# 13_Temp.net
KiCad netlist of a schematic drawn in Altium Designer
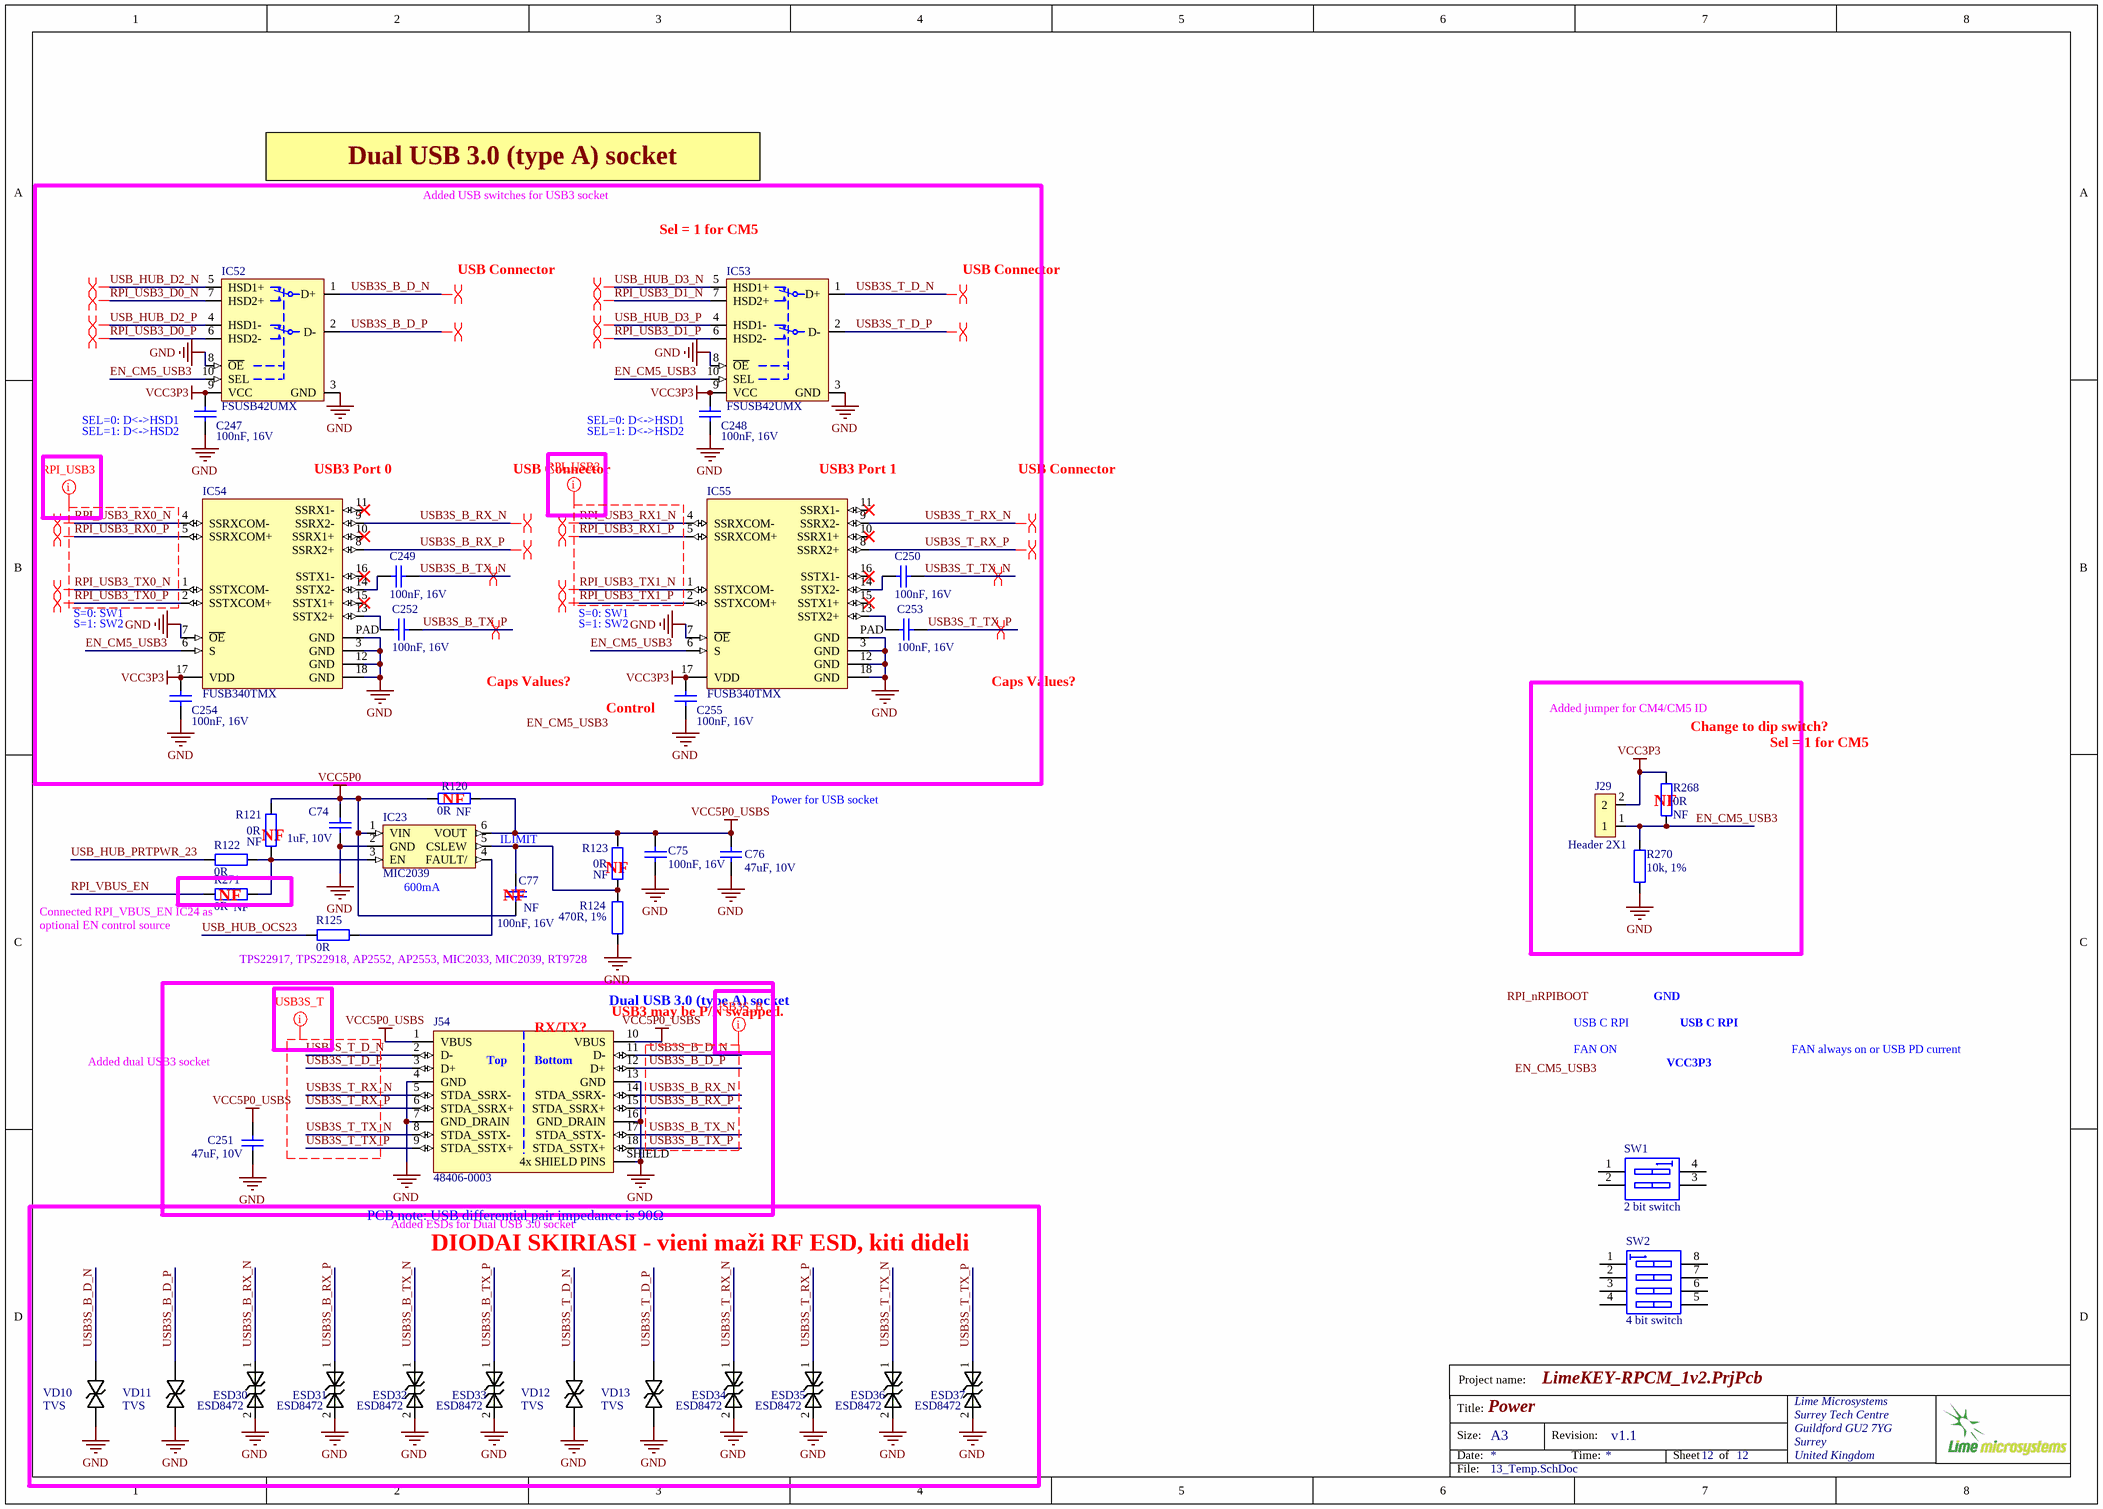
[diagram p0: 13_Temp.SchDoc]

(export (version "E")
  (design (tool "Eeschema 10.0.6"))
  (components
    (comp (ref "C74")
      (value "1uF, 10V")
      (footprint "CAP0402")
      (fields (field (name "MANUFACTURER") "Yageo"))
      (libsource (lib "") (part "Cap_0402_1"))
    )
    (comp (ref "C75")
      (value "100nF, 16V")
      (footprint "CAP0402")
      (fields
        (field (name "MANUFACTURER") "Murata Electronics")
        (field (name "TOLERANCE") "10 %")
        (field (name "MANUFACTURER PART NUMBER") "GRM155R71C104KA88D")
      )
      (libsource (lib "") (part "Cap_0402_1"))
    )
    (comp (ref "C76")
      (value "47uF, 10V")
      (footprint "CAP1206")
      (fields (field (name "TOLERANCE") "±20%") (field (name "MANUFACTURER") "TDK Corporation"))
      (libsource (lib "LimeFPGAboard_schLib") (part "Cap_1206"))
    )
    (comp (ref "C77")
      (value "100nF, 16V")
      (footprint "CAP0402")
      (fields
        (field (name "ASSEMBLY INFO") "NF")
        (field (name "MANUFACTURER") "Murata Electronics")
        (field (name "TOLERANCE") "10 %")
        (field (name "MANUFACTURER PART NUMBER") "GRM155R71C104KA88D")
      )
      (libsource (lib "") (part "Cap_0402_1"))
    )
    (comp (ref "C247")
      (value "100nF, 16V")
      (footprint "CAP0402")
      (fields
        (field (name "MANUFACTURER") "Murata Electronics")
        (field (name "TOLERANCE") "10 %")
        (field (name "MANUFACTURER PART NUMBER") "GRM155R71C104KA88D")
      )
      (libsource (lib "LimeMicroAltiumLib_schLib") (part "Cap_0402"))
    )
    (comp (ref "C248")
      (value "100nF, 16V")
      (footprint "CAP0402")
      (fields
        (field (name "MANUFACTURER") "Murata Electronics")
        (field (name "TOLERANCE") "10 %")
        (field (name "MANUFACTURER PART NUMBER") "GRM155R71C104KA88D")
      )
      (libsource (lib "LimeMicroAltiumLib_schLib") (part "Cap_0402"))
    )
    (comp (ref "C249")
      (value "100nF, 16V")
      (footprint "CAP0402")
      (fields
        (field (name "MANUFACTURER") "Murata Electronics")
        (field (name "TOLERANCE") "10 %")
        (field (name "MANUFACTURER PART NUMBER") "GRM155R71C104KA88D")
      )
      (libsource (lib "LimeMicroAltiumLib_schLib") (part "Cap_0402"))
    )
    (comp (ref "C250")
      (value "100nF, 16V")
      (footprint "CAP0402")
      (fields
        (field (name "MANUFACTURER") "Murata Electronics")
        (field (name "TOLERANCE") "10 %")
        (field (name "MANUFACTURER PART NUMBER") "GRM155R71C104KA88D")
      )
      (libsource (lib "LimeMicroAltiumLib_schLib") (part "Cap_0402"))
    )
    (comp (ref "C251")
      (value "47uF, 10V")
      (footprint "CAP1206")
      (fields (field (name "TOLERANCE") "±20%") (field (name "MANUFACTURER") "TDK Corporation"))
      (libsource (lib "LimeFPGAboard_schLib") (part "Cap_1206"))
    )
    (comp (ref "C252")
      (value "100nF, 16V")
      (footprint "CAP0402")
      (fields
        (field (name "MANUFACTURER") "Murata Electronics")
        (field (name "TOLERANCE") "10 %")
        (field (name "MANUFACTURER PART NUMBER") "GRM155R71C104KA88D")
      )
      (libsource (lib "LimeMicroAltiumLib_schLib") (part "Cap_0402"))
    )
    (comp (ref "C253")
      (value "100nF, 16V")
      (footprint "CAP0402")
      (fields
        (field (name "MANUFACTURER") "Murata Electronics")
        (field (name "TOLERANCE") "10 %")
        (field (name "MANUFACTURER PART NUMBER") "GRM155R71C104KA88D")
      )
      (libsource (lib "LimeMicroAltiumLib_schLib") (part "Cap_0402"))
    )
    (comp (ref "C254")
      (value "100nF, 16V")
      (footprint "CAP0402")
      (fields
        (field (name "MANUFACTURER") "Murata Electronics")
        (field (name "TOLERANCE") "10 %")
        (field (name "MANUFACTURER PART NUMBER") "GRM155R71C104KA88D")
      )
      (libsource (lib "LimeMicroAltiumLib_schLib") (part "Cap_0402"))
    )
    (comp (ref "C255")
      (value "100nF, 16V")
      (footprint "CAP0402")
      (fields
        (field (name "MANUFACTURER") "Murata Electronics")
        (field (name "TOLERANCE") "10 %")
        (field (name "MANUFACTURER PART NUMBER") "GRM155R71C104KA88D")
      )
      (libsource (lib "LimeMicroAltiumLib_schLib") (part "Cap_0402"))
    )
    (comp (ref "ESD30")
      (value "ESD8472")
      (footprint "ESD8472_X3DFN2")
      (fields (field (name "MANUFACTURER") "ON Semiconductor"))
      (libsource (lib "LimeMicroAltiumLib_schLib") (part "ESD8472"))
    )
    (comp (ref "ESD31")
      (value "ESD8472")
      (footprint "ESD8472_X3DFN2")
      (fields (field (name "MANUFACTURER") "ON Semiconductor"))
      (libsource (lib "LimeMicroAltiumLib_schLib") (part "ESD8472"))
    )
    (comp (ref "ESD32")
      (value "ESD8472")
      (footprint "ESD8472_X3DFN2")
      (fields (field (name "MANUFACTURER") "ON Semiconductor"))
      (libsource (lib "LimeMicroAltiumLib_schLib") (part "ESD8472"))
    )
    (comp (ref "ESD33")
      (value "ESD8472")
      (footprint "ESD8472_X3DFN2")
      (fields (field (name "MANUFACTURER") "ON Semiconductor"))
      (libsource (lib "LimeMicroAltiumLib_schLib") (part "ESD8472"))
    )
    (comp (ref "ESD34")
      (value "ESD8472")
      (footprint "ESD8472_X3DFN2")
      (fields (field (name "MANUFACTURER") "ON Semiconductor"))
      (libsource (lib "LimeMicroAltiumLib_schLib") (part "ESD8472"))
    )
    (comp (ref "ESD35")
      (value "ESD8472")
      (footprint "ESD8472_X3DFN2")
      (fields (field (name "MANUFACTURER") "ON Semiconductor"))
      (libsource (lib "LimeMicroAltiumLib_schLib") (part "ESD8472"))
    )
    (comp (ref "ESD36")
      (value "ESD8472")
      (footprint "ESD8472_X3DFN2")
      (fields (field (name "MANUFACTURER") "ON Semiconductor"))
      (libsource (lib "LimeMicroAltiumLib_schLib") (part "ESD8472"))
    )
    (comp (ref "ESD37")
      (value "ESD8472")
      (footprint "ESD8472_X3DFN2")
      (fields (field (name "MANUFACTURER") "ON Semiconductor"))
      (libsource (lib "LimeMicroAltiumLib_schLib") (part "ESD8472"))
    )
    (comp (ref "IC23")
      (value "MIC2039")
      (footprint "SOT23-6")
      (fields (field (name "MANUFACTURER") "Microchip"))
      (libsource (lib "LimeMicroAltiumLib_schLib_r04") (part "MIC2033_power_switch"))
    )
    (comp (ref "IC52")
      (value "FSUSB42UMX")
      (footprint "FSUSB42UMX")
      (fields (field (name "MANUFACTURER") "ON Semiconductor") (field (name "BASE PART NUMBER") "FSUSB42"))
      (libsource (lib "LimeMicroAltiumLib_schLib_r01") (part "FSUSB42UMX"))
    )
    (comp (ref "IC53")
      (value "FSUSB42UMX")
      (footprint "FSUSB42UMX")
      (fields (field (name "MANUFACTURER") "ON Semiconductor") (field (name "BASE PART NUMBER") "FSUSB42"))
      (libsource (lib "LimeMicroAltiumLib_schLib_r01") (part "FSUSB42UMX"))
    )
    (comp (ref "IC54")
      (value "FUSB340TMX")
      (footprint "FUSB340TMX_USB_switch_18-XFQFN")
      (fields (field (name "MANUFACTURER") "ON Semiconductor / Fairchild"))
      (libsource (lib "LimeMicroAltiumLib") (part "FUSB340TMX_USB_switch"))
    )
    (comp (ref "IC55")
      (value "FUSB340TMX")
      (footprint "FUSB340TMX_USB_switch_18-XFQFN")
      (fields (field (name "MANUFACTURER") "ON Semiconductor / Fairchild"))
      (libsource (lib "LimeMicroAltiumLib") (part "FUSB340TMX_USB_switch"))
    )
    (comp (ref "J29")
      (value "Header 2X1")
      (footprint "HDR_1x2")
      (fields (field (name "MANUFACTURER") "3M"))
      (libsource (lib "LimeFPGAboard_schLib") (part "Jumper"))
    )
    (comp (ref "J54")
      (value "48406-0003")
      (footprint "Dual_USB_48406-0003_Molex")
      (fields (field (name "MANUFACTURER") "Molex"))
      (libsource (lib "LimeMicroAltiumLib") (part "Dual_USB_48406-0003_Molex"))
    )
    (comp (ref "R120")
      (value "0R")
      (footprint "RES0402")
      (fields
        (field (name "ASSEMBLY INFO") "NF")
        (field (name "MANUFACTURER") "Yageo")
        (field (name "TOLERANCE") "Jumper")
      )
      (libsource (lib "LimeMicroAltiumLib_schLib") (part "Res_0402"))
    )
    (comp (ref "R121")
      (value "0R")
      (footprint "RES0402")
      (fields
        (field (name "ASSEMBLY INFO") "NF")
        (field (name "MANUFACTURER") "Yageo")
        (field (name "TOLERANCE") "Jumper")
      )
      (libsource (lib "LimeMicroAltiumLib_schLib") (part "Res_0402"))
    )
    (comp (ref "R122")
      (value "0R")
      (footprint "RES0402")
      (fields (field (name "MANUFACTURER") "Yageo") (field (name "TOLERANCE") "Jumper"))
      (libsource (lib "LimeMicroAltiumLib_schLib") (part "Res_0402"))
    )
    (comp (ref "R123")
      (value "0R")
      (footprint "RES0402")
      (fields
        (field (name "ASSEMBLY INFO") "NF")
        (field (name "MANUFACTURER") "Yageo")
        (field (name "TOLERANCE") "Jumper")
      )
      (libsource (lib "LimeMicroAltiumLib_schLib") (part "Res_0402"))
    )
    (comp (ref "R124")
      (value "470R, 1%")
      (footprint "RES0402")
      (fields (field (name "TOLERANCE") "1%") (field (name "MANUFACTURER") "Yageo"))
      (libsource (lib "LimeMicroAltiumLib_schLib") (part "Res_0402"))
    )
    (comp (ref "R125")
      (value "0R")
      (footprint "RES0402")
      (fields (field (name "MANUFACTURER") "Yageo") (field (name "TOLERANCE") "Jumper"))
      (libsource (lib "LimeMicroAltiumLib_schLib") (part "Res_0402"))
    )
    (comp (ref "R268")
      (value "0R")
      (footprint "RES0402")
      (fields
        (field (name "ASSEMBLY INFO") "NF")
        (field (name "MANUFACTURER") "Yageo")
        (field (name "TOLERANCE") "Jumper")
      )
      (libsource (lib "") (part "Res_0402_1"))
    )
    (comp (ref "R270")
      (value "10k, 1%")
      (footprint "RES0402")
      (fields (field (name "MANUFACTURER") "Yageo") (field (name "TOLERANCE") "±1%"))
      (libsource (lib "") (part "Res_0402_1"))
    )
    (comp (ref "R271")
      (value "0R")
      (footprint "RES0402")
      (fields
        (field (name "ASSEMBLY INFO") "NF")
        (field (name "MANUFACTURER") "Yageo")
        (field (name "TOLERANCE") "Jumper")
      )
      (libsource (lib "LimeMicroAltiumLib_schLib") (part "Res_0402"))
    )
    (comp (ref "SW1")
      (value "2 bit switch")
      (footprint "SW_2WAY_SMD_1P27")
      (fields (field (name "MANUFACTURER") "TE Connectivity Alcoswitch Switches"))
      (libsource (lib "LimeMicroAltiumLib") (part "SW_SM_2bit"))
    )
    (comp (ref "SW2")
      (value "4 bit switch")
      (footprint "SW_4WAY_SMD_1P27")
      (fields (field (name "MANUFACTURER") "Omron Electronics Inc-EMC Div"))
      (libsource (lib "LimeMicroAltiumLib") (part "SW_SM_4bit"))
    )
    (comp (ref "VD10")
      (value "TVS")
      (footprint "SOD323")
      (fields
        (field (name "MANUFACTURER PART NUMBER") "SD03LCC")
        (field (name "MANUFACTURER") "Sangdest Microelectronics")
      )
      (libsource (lib "LimeNet-Micro_2v1-SDR") (part "DIODE_TVS"))
    )
    (comp (ref "VD11")
      (value "TVS")
      (footprint "SOD323")
      (fields
        (field (name "MANUFACTURER PART NUMBER") "SD03LCC")
        (field (name "MANUFACTURER") "Sangdest Microelectronics")
      )
      (libsource (lib "LimeNet-Micro_2v1-SDR") (part "DIODE_TVS"))
    )
    (comp (ref "VD12")
      (value "TVS")
      (footprint "SOD323")
      (fields
        (field (name "MANUFACTURER PART NUMBER") "SD03LCC")
        (field (name "MANUFACTURER") "Sangdest Microelectronics")
      )
      (libsource (lib "LimeNet-Micro_2v1-SDR") (part "DIODE_TVS"))
    )
    (comp (ref "VD13")
      (value "TVS")
      (footprint "SOD323")
      (fields
        (field (name "MANUFACTURER PART NUMBER") "SD03LCC")
        (field (name "MANUFACTURER") "Sangdest Microelectronics")
      )
      (libsource (lib "LimeNet-Micro_2v1-SDR") (part "DIODE_TVS"))
    )
  )
  (nets
    (net (code "1") (name "/EN_CM5_USB3") (class "Default")
      (node (ref "IC52") (pin "10") (pinfunction "SEL_10") (pintype "input"))
      (node (ref "IC53") (pin "10") (pinfunction "SEL_10") (pintype "input"))
      (node (ref "IC54") (pin "6") (pinfunction "S_6") (pintype "input"))
      (node (ref "IC55") (pin "6") (pinfunction "S_6") (pintype "input"))
      (node (ref "J29") (pin "1") (pinfunction "1_1") (pintype "passive"))
      (node (ref "R268") (pin "1") (pinfunction "1_1") (pintype "passive"))
      (node (ref "R270") (pin "1") (pinfunction "1_1") (pintype "passive"))
    )
    (net (code "2") (name "/RPI_USB3_D0_N") (class "Default")
      (node (ref "IC52") (pin "7") (pinfunction "HSD2+_7") (pintype "passive"))
    )
    (net (code "3") (name "/RPI_USB3_D0_P") (class "Default")
      (node (ref "IC52") (pin "6") (pinfunction "HSD2-_6") (pintype "passive"))
    )
    (net (code "4") (name "/RPI_USB3_D1_N") (class "Default")
      (node (ref "IC53") (pin "7") (pinfunction "HSD2+_7") (pintype "passive"))
    )
    (net (code "5") (name "/RPI_USB3_D1_P") (class "Default")
      (node (ref "IC53") (pin "6") (pinfunction "HSD2-_6") (pintype "passive"))
    )
    (net (code "6") (name "/RPI_USB3_RX0_N") (class "Default")
      (node (ref "IC54") (pin "4") (pinfunction "SSRXCOM-_4") (pintype "bidirectional"))
    )
    (net (code "7") (name "/RPI_USB3_RX0_P") (class "Default")
      (node (ref "IC54") (pin "5") (pinfunction "SSRXCOM+_5") (pintype "bidirectional"))
    )
    (net (code "8") (name "/RPI_USB3_RX1_N") (class "Default")
      (node (ref "IC55") (pin "4") (pinfunction "SSRXCOM-_4") (pintype "bidirectional"))
    )
    (net (code "9") (name "/RPI_USB3_RX1_P") (class "Default")
      (node (ref "IC55") (pin "5") (pinfunction "SSRXCOM+_5") (pintype "bidirectional"))
    )
    (net (code "10") (name "/RPI_USB3_TX0_N") (class "Default")
      (node (ref "IC54") (pin "1") (pinfunction "SSTXCOM-_1") (pintype "bidirectional"))
    )
    (net (code "11") (name "/RPI_USB3_TX0_P") (class "Default")
      (node (ref "IC54") (pin "2") (pinfunction "SSTXCOM+_2") (pintype "bidirectional"))
    )
    (net (code "12") (name "/RPI_USB3_TX1_N") (class "Default")
      (node (ref "IC55") (pin "1") (pinfunction "SSTXCOM-_1") (pintype "bidirectional"))
    )
    (net (code "13") (name "/RPI_USB3_TX1_P") (class "Default")
      (node (ref "IC55") (pin "2") (pinfunction "SSTXCOM+_2") (pintype "bidirectional"))
    )
    (net (code "14") (name "/RPI_VBUS_EN") (class "Default")
      (node (ref "R271") (pin "2") (pinfunction "2_2") (pintype "passive"))
    )
    (net (code "16") (name "/USB3S_B_D_N") (class "Default")
      (node (ref "IC52") (pin "1") (pinfunction "D+_1") (pintype "passive"))
      (node (ref "J54") (pin "11") (pinfunction "D-_11") (pintype "bidirectional"))
      (node (ref "VD10") (pin "A") (pinfunction "A_A") (pintype "passive"))
    )
    (net (code "17") (name "/USB3S_B_D_P") (class "Default")
      (node (ref "IC52") (pin "2") (pinfunction "D-_2") (pintype "passive"))
      (node (ref "J54") (pin "12") (pinfunction "D+_12") (pintype "bidirectional"))
      (node (ref "VD11") (pin "A") (pinfunction "A_A") (pintype "passive"))
    )
    (net (code "18") (name "/USB3S_B_RX_N") (class "Default")
      (node (ref "ESD30") (pin "1") (pinfunction "1_1") (pintype "passive"))
      (node (ref "IC54") (pin "9") (pinfunction "SSRX2-_9") (pintype "bidirectional"))
      (node (ref "J54") (pin "14") (pinfunction "STDA_SSRX-_14") (pintype "bidirectional"))
    )
    (net (code "19") (name "/USB3S_B_RX_P") (class "Default")
      (node (ref "ESD31") (pin "1") (pinfunction "1_1") (pintype "passive"))
      (node (ref "IC54") (pin "8") (pinfunction "SSRX2+_8") (pintype "bidirectional"))
      (node (ref "J54") (pin "15") (pinfunction "STDA_SSRX+_15") (pintype "bidirectional"))
    )
    (net (code "20") (name "/USB3S_B_TX_N") (class "Default")
      (node (ref "C249") (pin "2") (pinfunction "2_2") (pintype "passive"))
      (node (ref "ESD32") (pin "1") (pinfunction "1_1") (pintype "passive"))
      (node (ref "J54") (pin "17") (pinfunction "STDA_SSTX-_17") (pintype "bidirectional"))
    )
    (net (code "21") (name "/USB3S_B_TX_P") (class "Default")
      (node (ref "C252") (pin "2") (pinfunction "2_2") (pintype "passive"))
      (node (ref "ESD33") (pin "1") (pinfunction "1_1") (pintype "passive"))
      (node (ref "J54") (pin "18") (pinfunction "STDA_SSTX+_18") (pintype "bidirectional"))
    )
    (net (code "22") (name "/USB3S_T_D_N") (class "Default")
      (node (ref "IC53") (pin "1") (pinfunction "D+_1") (pintype "passive"))
      (node (ref "J54") (pin "2") (pinfunction "D-_2") (pintype "bidirectional"))
      (node (ref "VD12") (pin "A") (pinfunction "A_A") (pintype "passive"))
    )
    (net (code "23") (name "/USB3S_T_D_P") (class "Default")
      (node (ref "IC53") (pin "2") (pinfunction "D-_2") (pintype "passive"))
      (node (ref "J54") (pin "3") (pinfunction "D+_3") (pintype "bidirectional"))
      (node (ref "VD13") (pin "A") (pinfunction "A_A") (pintype "passive"))
    )
    (net (code "24") (name "/USB3S_T_RX_N") (class "Default")
      (node (ref "ESD34") (pin "1") (pinfunction "1_1") (pintype "passive"))
      (node (ref "IC55") (pin "9") (pinfunction "SSRX2-_9") (pintype "bidirectional"))
      (node (ref "J54") (pin "5") (pinfunction "STDA_SSRX-_5") (pintype "bidirectional"))
    )
    (net (code "25") (name "/USB3S_T_RX_P") (class "Default")
      (node (ref "ESD35") (pin "1") (pinfunction "1_1") (pintype "passive"))
      (node (ref "IC55") (pin "8") (pinfunction "SSRX2+_8") (pintype "bidirectional"))
      (node (ref "J54") (pin "6") (pinfunction "STDA_SSRX+_6") (pintype "bidirectional"))
    )
    (net (code "26") (name "/USB3S_T_TX_N") (class "Default")
      (node (ref "C250") (pin "2") (pinfunction "2_2") (pintype "passive"))
      (node (ref "ESD36") (pin "1") (pinfunction "1_1") (pintype "passive"))
      (node (ref "J54") (pin "8") (pinfunction "STDA_SSTX-_8") (pintype "bidirectional"))
    )
    (net (code "27") (name "/USB3S_T_TX_P") (class "Default")
      (node (ref "C253") (pin "2") (pinfunction "2_2") (pintype "passive"))
      (node (ref "ESD37") (pin "1") (pinfunction "1_1") (pintype "passive"))
      (node (ref "J54") (pin "9") (pinfunction "STDA_SSTX+_9") (pintype "bidirectional"))
    )
    (net (code "28") (name "/USB_HUB_D2_N") (class "Default")
      (node (ref "IC52") (pin "5") (pinfunction "HSD1+_5") (pintype "passive"))
    )
    (net (code "29") (name "/USB_HUB_D2_P") (class "Default")
      (node (ref "IC52") (pin "4") (pinfunction "HSD1-_4") (pintype "passive"))
    )
    (net (code "30") (name "/USB_HUB_D3_N") (class "Default")
      (node (ref "IC53") (pin "5") (pinfunction "HSD1+_5") (pintype "passive"))
    )
    (net (code "31") (name "/USB_HUB_D3_P") (class "Default")
      (node (ref "IC53") (pin "4") (pinfunction "HSD1-_4") (pintype "passive"))
    )
    (net (code "32") (name "/USB_HUB_OCS23") (class "Default")
      (node (ref "R125") (pin "2") (pinfunction "2_2") (pintype "passive"))
    )
    (net (code "33") (name "/USB_HUB_PRTPWR_23") (class "Default")
      (node (ref "R122") (pin "2") (pinfunction "2_2") (pintype "passive"))
    )
    (net (code "34") (name "GND") (class "Default")
      (node (ref "C247") (pin "2") (pinfunction "2_2") (pintype "passive"))
      (node (ref "C248") (pin "2") (pinfunction "2_2") (pintype "passive"))
      (node (ref "C251") (pin "1") (pinfunction "1_1") (pintype "passive"))
      (node (ref "C254") (pin "2") (pinfunction "2_2") (pintype "passive"))
      (node (ref "C255") (pin "2") (pinfunction "2_2") (pintype "passive"))
      (node (ref "C74") (pin "2") (pinfunction "2_2") (pintype "passive"))
      (node (ref "C75") (pin "2") (pinfunction "2_2") (pintype "passive"))
      (node (ref "C76") (pin "1") (pinfunction "1_1") (pintype "passive"))
      (node (ref "ESD30") (pin "2") (pinfunction "2_2") (pintype "passive"))
      (node (ref "ESD31") (pin "2") (pinfunction "2_2") (pintype "passive"))
      (node (ref "ESD32") (pin "2") (pinfunction "2_2") (pintype "passive"))
      (node (ref "ESD33") (pin "2") (pinfunction "2_2") (pintype "passive"))
      (node (ref "ESD34") (pin "2") (pinfunction "2_2") (pintype "passive"))
      (node (ref "ESD35") (pin "2") (pinfunction "2_2") (pintype "passive"))
      (node (ref "ESD36") (pin "2") (pinfunction "2_2") (pintype "passive"))
      (node (ref "ESD37") (pin "2") (pinfunction "2_2") (pintype "passive"))
      (node (ref "IC23") (pin "2") (pinfunction "GND_2") (pintype "passive"))
      (node (ref "IC52") (pin "3") (pinfunction "GND_3") (pintype "passive"))
      (node (ref "IC52") (pin "8") (pinfunction "~{OE}_8") (pintype "input"))
      (node (ref "IC53") (pin "3") (pinfunction "GND_3") (pintype "passive"))
      (node (ref "IC53") (pin "8") (pinfunction "~{OE}_8") (pintype "input"))
      (node (ref "IC54") (pin "12") (pinfunction "GND_12") (pintype "passive"))
      (node (ref "IC54") (pin "18") (pinfunction "GND_18") (pintype "passive"))
      (node (ref "IC54") (pin "3") (pinfunction "GND_3") (pintype "passive"))
      (node (ref "IC54") (pin "7") (pinfunction "~{OE}_7") (pintype "input"))
      (node (ref "IC54") (pin "PAD") (pinfunction "GND_PAD") (pintype "passive"))
      (node (ref "IC55") (pin "12") (pinfunction "GND_12") (pintype "passive"))
      (node (ref "IC55") (pin "18") (pinfunction "GND_18") (pintype "passive"))
      (node (ref "IC55") (pin "3") (pinfunction "GND_3") (pintype "passive"))
      (node (ref "IC55") (pin "7") (pinfunction "~{OE}_7") (pintype "input"))
      (node (ref "IC55") (pin "PAD") (pinfunction "GND_PAD") (pintype "passive"))
      (node (ref "J54") (pin "13") (pinfunction "GND_13") (pintype "passive"))
      (node (ref "J54") (pin "16") (pinfunction "GND_DRAIN_16") (pintype "passive"))
      (node (ref "J54") (pin "4") (pinfunction "GND_4") (pintype "passive"))
      (node (ref "J54") (pin "7") (pinfunction "GND_DRAIN_7") (pintype "passive"))
      (node (ref "J54") (pin "SHIELD") (pinfunction "4x_SHIELD_PINS_SHIELD") (pintype "passive"))
      (node (ref "R124") (pin "1") (pinfunction "1_1") (pintype "passive"))
      (node (ref "R270") (pin "2") (pinfunction "2_2") (pintype "passive"))
      (node (ref "VD10") (pin "K") (pinfunction "K_K") (pintype "passive"))
      (node (ref "VD11") (pin "K") (pinfunction "K_K") (pintype "passive"))
      (node (ref "VD12") (pin "K") (pinfunction "K_K") (pintype "passive"))
      (node (ref "VD13") (pin "K") (pinfunction "K_K") (pintype "passive"))
    )
    (net (code "35") (name "Net-(IC23-CSLEW)") (class "Default")
      (node (ref "C77") (pin "1") (pinfunction "1_1") (pintype "passive"))
      (node (ref "IC23") (pin "5") (pinfunction "CSLEW_5") (pintype "output"))
      (node (ref "R123") (pin "1") (pinfunction "1_1") (pintype "passive"))
      (node (ref "R124") (pin "2") (pinfunction "2_2") (pintype "passive"))
    )
    (net (code "36") (name "Net-(IC23-EN)") (class "Default")
      (node (ref "IC23") (pin "3") (pinfunction "EN_3") (pintype "input"))
      (node (ref "R121") (pin "1") (pinfunction "1_1") (pintype "passive"))
      (node (ref "R122") (pin "1") (pinfunction "1_1") (pintype "passive"))
      (node (ref "R271") (pin "1") (pinfunction "1_1") (pintype "passive"))
    )
    (net (code "37") (name "Net-(IC23-FAULT{slash})") (class "Default")
      (node (ref "IC23") (pin "4") (pinfunction "FAULT/_4") (pintype "output"))
      (node (ref "R125") (pin "1") (pinfunction "1_1") (pintype "passive"))
    )
    (net (code "38") (name "Net-(IC54-SSTX2+)") (class "Default")
      (node (ref "C252") (pin "1") (pinfunction "1_1") (pintype "passive"))
      (node (ref "IC54") (pin "13") (pinfunction "SSTX2+_13") (pintype "bidirectional"))
    )
    (net (code "39") (name "Net-(IC54-SSTX2-)") (class "Default")
      (node (ref "C249") (pin "1") (pinfunction "1_1") (pintype "passive"))
      (node (ref "IC54") (pin "14") (pinfunction "SSTX2-_14") (pintype "bidirectional"))
    )
    (net (code "40") (name "Net-(IC55-SSTX2+)") (class "Default")
      (node (ref "C253") (pin "1") (pinfunction "1_1") (pintype "passive"))
      (node (ref "IC55") (pin "13") (pinfunction "SSTX2+_13") (pintype "bidirectional"))
    )
    (net (code "41") (name "Net-(IC55-SSTX2-)") (class "Default")
      (node (ref "C250") (pin "1") (pinfunction "1_1") (pintype "passive"))
      (node (ref "IC55") (pin "14") (pinfunction "SSTX2-_14") (pintype "bidirectional"))
    )
    (net (code "42") (name "VCC3P3") (class "Default")
      (node (ref "C247") (pin "1") (pinfunction "1_1") (pintype "passive"))
      (node (ref "C248") (pin "1") (pinfunction "1_1") (pintype "passive"))
      (node (ref "C254") (pin "1") (pinfunction "1_1") (pintype "passive"))
      (node (ref "C255") (pin "1") (pinfunction "1_1") (pintype "passive"))
      (node (ref "IC52") (pin "9") (pinfunction "VCC_9") (pintype "power_in"))
      (node (ref "IC53") (pin "9") (pinfunction "VCC_9") (pintype "power_in"))
      (node (ref "IC54") (pin "17") (pinfunction "VDD_17") (pintype "power_in"))
      (node (ref "IC55") (pin "17") (pinfunction "VDD_17") (pintype "power_in"))
      (node (ref "J29") (pin "2") (pinfunction "2_2") (pintype "passive"))
      (node (ref "R268") (pin "2") (pinfunction "2_2") (pintype "passive"))
    )
    (net (code "43") (name "VCC5P0") (class "Default")
      (node (ref "C74") (pin "1") (pinfunction "1_1") (pintype "passive"))
      (node (ref "C77") (pin "2") (pinfunction "2_2") (pintype "passive"))
      (node (ref "IC23") (pin "1") (pinfunction "VIN_1") (pintype "input"))
      (node (ref "R120") (pin "2") (pinfunction "2_2") (pintype "passive"))
      (node (ref "R121") (pin "2") (pinfunction "2_2") (pintype "passive"))
    )
    (net (code "44") (name "VCC5P0_USBS") (class "Default")
      (node (ref "C251") (pin "2") (pinfunction "2_2") (pintype "passive"))
      (node (ref "C75") (pin "1") (pinfunction "1_1") (pintype "passive"))
      (node (ref "C76") (pin "2") (pinfunction "2_2") (pintype "passive"))
      (node (ref "IC23") (pin "6") (pinfunction "VOUT_6") (pintype "output"))
      (node (ref "J54") (pin "1") (pinfunction "VBUS_1") (pintype "power_in"))
      (node (ref "J54") (pin "10") (pinfunction "VBUS_10") (pintype "power_in"))
      (node (ref "R120") (pin "1") (pinfunction "1_1") (pintype "passive"))
      (node (ref "R123") (pin "2") (pinfunction "2_2") (pintype "passive"))
    )
    (net (code "45") (name "unconnected-(IC54-SSRX1+-Pad10)") (class "Default")
      (node (ref "IC54") (pin "10") (pinfunction "SSRX1+_10") (pintype "bidirectional+no_connect"))
    )
    (net (code "46") (name "unconnected-(IC54-SSRX1--Pad11)") (class "Default")
      (node (ref "IC54") (pin "11") (pinfunction "SSRX1-_11") (pintype "bidirectional+no_connect"))
    )
    (net (code "47") (name "unconnected-(IC54-SSTX1+-Pad15)") (class "Default")
      (node (ref "IC54") (pin "15") (pinfunction "SSTX1+_15") (pintype "bidirectional+no_connect"))
    )
    (net (code "48") (name "unconnected-(IC54-SSTX1--Pad16)") (class "Default")
      (node (ref "IC54") (pin "16") (pinfunction "SSTX1-_16") (pintype "bidirectional+no_connect"))
    )
    (net (code "49") (name "unconnected-(IC55-SSRX1+-Pad10)") (class "Default")
      (node (ref "IC55") (pin "10") (pinfunction "SSRX1+_10") (pintype "bidirectional+no_connect"))
    )
    (net (code "50") (name "unconnected-(IC55-SSRX1--Pad11)") (class "Default")
      (node (ref "IC55") (pin "11") (pinfunction "SSRX1-_11") (pintype "bidirectional+no_connect"))
    )
    (net (code "51") (name "unconnected-(IC55-SSTX1+-Pad15)") (class "Default")
      (node (ref "IC55") (pin "15") (pinfunction "SSTX1+_15") (pintype "bidirectional+no_connect"))
    )
    (net (code "52") (name "unconnected-(IC55-SSTX1--Pad16)") (class "Default")
      (node (ref "IC55") (pin "16") (pinfunction "SSTX1-_16") (pintype "bidirectional+no_connect"))
    )
    (net (code "53") (name "unconnected-(SW1-A1-Pad1)") (class "Default")
      (node (ref "SW1") (pin "1") (pinfunction "A1_1") (pintype "passive"))
    )
    (net (code "54") (name "unconnected-(SW1-A2-Pad2)") (class "Default")
      (node (ref "SW1") (pin "2") (pinfunction "A2_2") (pintype "passive"))
    )
    (net (code "55") (name "unconnected-(SW1-B1-Pad4)") (class "Default")
      (node (ref "SW1") (pin "4") (pinfunction "B1_4") (pintype "passive"))
    )
    (net (code "56") (name "unconnected-(SW1-B2-Pad3)") (class "Default")
      (node (ref "SW1") (pin "3") (pinfunction "B2_3") (pintype "passive"))
    )
    (net (code "57") (name "unconnected-(SW2-A1-Pad1)") (class "Default")
      (node (ref "SW2") (pin "1") (pinfunction "A1_1") (pintype "passive"))
    )
    (net (code "58") (name "unconnected-(SW2-A2-Pad2)") (class "Default")
      (node (ref "SW2") (pin "2") (pinfunction "A2_2") (pintype "passive"))
    )
    (net (code "59") (name "unconnected-(SW2-A3-Pad3)") (class "Default")
      (node (ref "SW2") (pin "3") (pinfunction "A3_3") (pintype "passive"))
    )
    (net (code "60") (name "unconnected-(SW2-A4-Pad4)") (class "Default")
      (node (ref "SW2") (pin "4") (pinfunction "A4_4") (pintype "passive"))
    )
    (net (code "61") (name "unconnected-(SW2-B1-Pad8)") (class "Default")
      (node (ref "SW2") (pin "8") (pinfunction "B1_8") (pintype "passive"))
    )
    (net (code "62") (name "unconnected-(SW2-B2-Pad7)") (class "Default")
      (node (ref "SW2") (pin "7") (pinfunction "B2_7") (pintype "passive"))
    )
    (net (code "63") (name "unconnected-(SW2-B3-Pad6)") (class "Default")
      (node (ref "SW2") (pin "6") (pinfunction "B3_6") (pintype "passive"))
    )
    (net (code "64") (name "unconnected-(SW2-B4-Pad5)") (class "Default")
      (node (ref "SW2") (pin "5") (pinfunction "B4_5") (pintype "passive"))
    )
  )
)
